# mapleCUL_small-V10_59.net
KiCad netlist of a schematic drawn in EAGLE
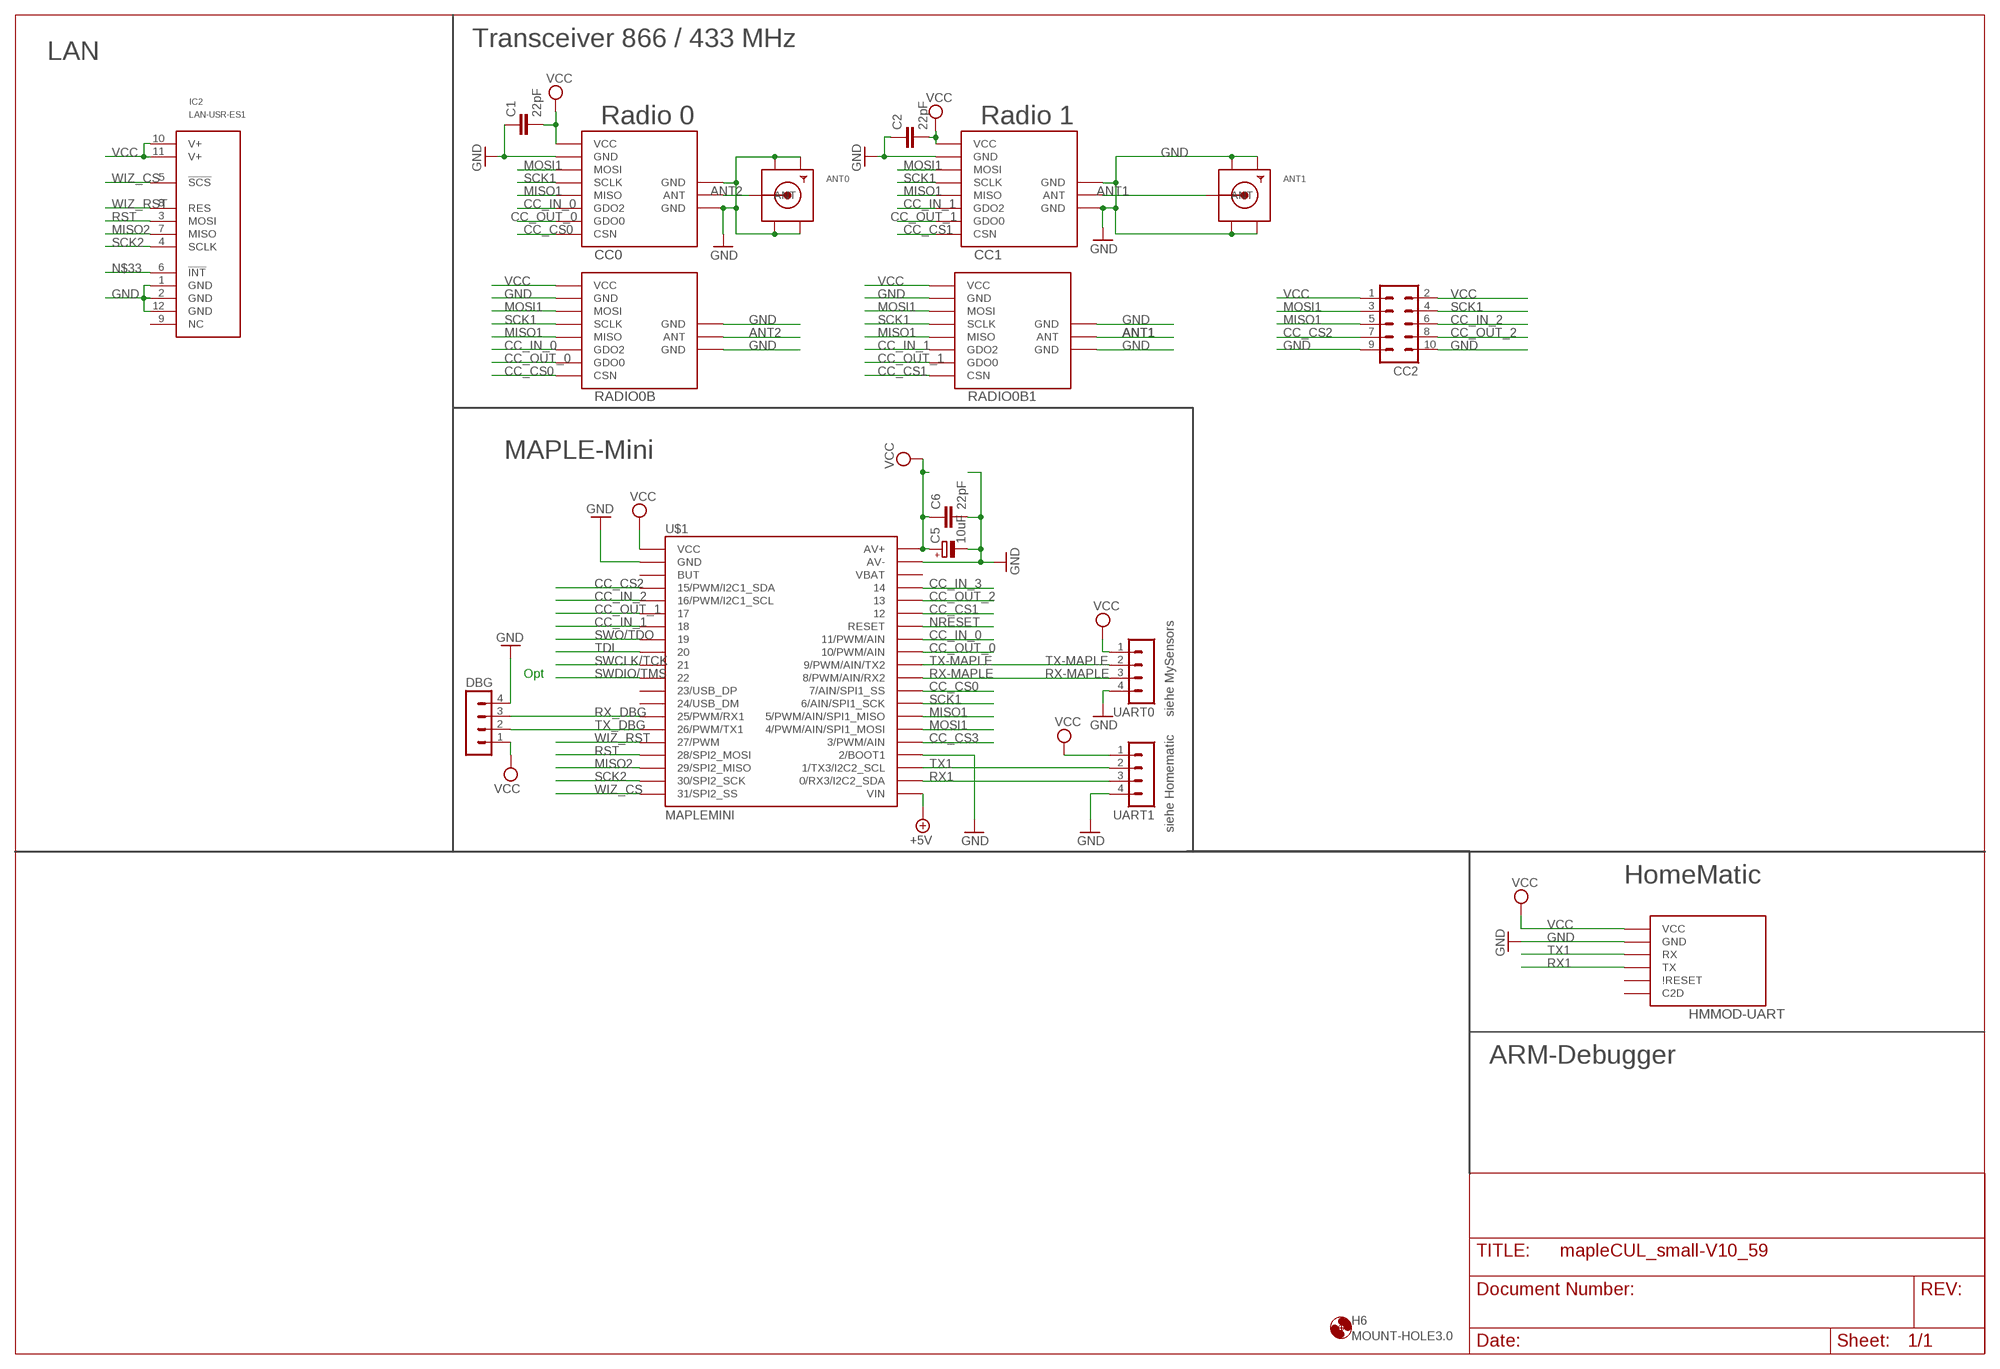
[diagram p0: schematic, sheet 1]

(export (version "E")
  (design (tool "Eeschema 10.0.6"))
  (components
    (comp (ref "ANT0")
      (value "SMACONNECTOR_EDGE_UFL")
      (footprint "eagle-import:SMA_EDGELAUNCH_UFL")
      (libsource (lib "eagle-import") (part "SMACONNECTOR_EDGE_UFL"))
    )
    (comp (ref "ANT1")
      (value "SMACONNECTOR_EDGE_UFL")
      (footprint "eagle-import:SMA_EDGELAUNCH_UFL")
      (libsource (lib "eagle-import") (part "SMACONNECTOR_EDGE_UFL"))
    )
    (comp (ref "C1")
      (value "22pF")
      (footprint "eagle-import:C0805")
      (libsource (lib "eagle-import") (part "C-EUC0805"))
    )
    (comp (ref "C2")
      (value "22pF")
      (footprint "eagle-import:C0805")
      (libsource (lib "eagle-import") (part "C-EUC0805"))
    )
    (comp (ref "C5")
      (value "10uF")
      (footprint "eagle-import:R_2012-12W")
      (libsource (lib "eagle-import") (part "CPOL-EUR/2012-12W"))
    )
    (comp (ref "C6")
      (value "22pF")
      (footprint "eagle-import:C0805")
      (libsource (lib "eagle-import") (part "C-EUC0805"))
    )
    (comp (ref "CC0")
      (value "CC1101")
      (footprint "eagle-import:CC1101_MODULE1_SMD")
      (libsource (lib "eagle-import") (part "wireless_CC1101_MODULE1SMD"))
    )
    (comp (ref "CC1")
      (value "CC1101_MODULE1SMD")
      (footprint "eagle-import:CC1101_MODULE1_SMD")
      (libsource (lib "eagle-import") (part "wireless_CC1101_MODULE1SMD"))
    )
    (comp (ref "CC2")
      (value "MA05-2")
      (footprint "eagle-import:MA05-2")
      (libsource (lib "eagle-import") (part "MA05-2"))
    )
    (comp (ref "DBG")
      (value "MA04-1")
      (footprint "eagle-import:MA04-1")
      (libsource (lib "eagle-import") (part "MA04-1"))
    )
    (comp (ref "H6")
      (value "MOUNT-HOLE3.0")
      (footprint "eagle-import:3,0")
      (libsource (lib "eagle-import") (part "MOUNT-HOLE3.0"))
    )
    (comp (ref "HMMOD-UART")
      (value "HM-MOD-UARTDIL")
      (footprint "eagle-import:HM-MOD-UART-DIL")
      (libsource (lib "eagle-import") (part "HM-MOD-UARTDIL"))
    )
    (comp (ref "IC2")
      (value "LAN-USR-ES1")
      (footprint "eagle-import:USR-ES1")
      (libsource (lib "eagle-import") (part "LAN-USR-ES1"))
    )
    (comp (ref "RADIO0B")
      (value "CC1101_MODULE1SMALL")
      (footprint "eagle-import:CC1101_MODULE1_SMD")
      (libsource (lib "eagle-import") (part "CC1101_MODULE1SMALL"))
    )
    (comp (ref "RADIO0B1")
      (value "CC1101_MODULE1SMD")
      (footprint "eagle-import:CC1101_MODULE1_SMD")
      (libsource (lib "eagle-import") (part "CC1101_MODULE1SMD"))
    )
    (comp (ref "U$1")
      (value "MAPLEMINI")
      (footprint "eagle-import:20-DIP")
      (libsource (lib "eagle-import") (part "MAPLEMINI"))
    )
    (comp (ref "UART0")
      (value "MA04-1")
      (footprint "eagle-import:MA04-1")
      (libsource (lib "eagle-import") (part "MA04-1"))
    )
    (comp (ref "UART1")
      (value "MA04-1")
      (footprint "eagle-import:MA04-1")
      (libsource (lib "eagle-import") (part "MA04-1"))
    )
  )
  (nets
    (net (code "1") (name "+5V") (class "Default")
      (node (ref "U$1") (pin "21") (pinfunction "VIN_21") (pintype "bidirectional"))
    )
    (net (code "2") (name "/ANT1") (class "Default")
      (node (ref "ANT1") (pin "P") (pinfunction "ANT_P") (pintype "bidirectional"))
      (node (ref "CC1") (pin "ANT") (pinfunction "ANT_ANT") (pintype "output"))
      (node (ref "RADIO0B1") (pin "ANT") (pinfunction "ANT_ANT") (pintype "output"))
    )
    (net (code "3") (name "/ANT2") (class "Default")
      (node (ref "ANT0") (pin "P") (pinfunction "ANT_P") (pintype "bidirectional"))
      (node (ref "CC0") (pin "ANT") (pinfunction "ANT_ANT") (pintype "output"))
      (node (ref "RADIO0B") (pin "ANT") (pinfunction "ANT_ANT") (pintype "output"))
    )
    (net (code "4") (name "/CC_CS0") (class "Default")
      (node (ref "CC0") (pin "CSN") (pinfunction "CSN_CSN") (pintype "bidirectional"))
      (node (ref "RADIO0B") (pin "CSN") (pinfunction "CSN_CSN") (pintype "bidirectional"))
      (node (ref "U$1") (pin "29") (pinfunction "7/AIN/SPI1_SS_29") (pintype "bidirectional"))
    )
    (net (code "5") (name "/CC_CS1") (class "Default")
      (node (ref "CC1") (pin "CSN") (pinfunction "CSN_CSN") (pintype "bidirectional"))
      (node (ref "RADIO0B1") (pin "CSN") (pinfunction "CSN_CSN") (pintype "bidirectional"))
      (node (ref "U$1") (pin "35") (pinfunction "12_35") (pintype "bidirectional"))
    )
    (net (code "6") (name "/CC_CS2") (class "Default")
      (node (ref "CC2") (pin "7") (pinfunction "7_7") (pintype "passive"))
      (node (ref "U$1") (pin "4") (pinfunction "15/PWM/I2C1_SDA_4") (pintype "bidirectional"))
    )
    (net (code "7") (name "/CC_CS3") (class "Default")
      (node (ref "U$1") (pin "25") (pinfunction "3/PWM/AIN_25") (pintype "bidirectional"))
    )
    (net (code "8") (name "/CC_IN_0") (class "Default")
      (node (ref "CC0") (pin "GDO2") (pinfunction "GDO2_GDO2") (pintype "bidirectional"))
      (node (ref "RADIO0B") (pin "GDO2") (pinfunction "GDO2_GDO2") (pintype "bidirectional"))
      (node (ref "U$1") (pin "33") (pinfunction "11/PWM/AIN_33") (pintype "bidirectional"))
    )
    (net (code "9") (name "/CC_IN_1") (class "Default")
      (node (ref "CC1") (pin "GDO2") (pinfunction "GDO2_GDO2") (pintype "bidirectional"))
      (node (ref "RADIO0B1") (pin "GDO2") (pinfunction "GDO2_GDO2") (pintype "bidirectional"))
      (node (ref "U$1") (pin "7") (pinfunction "18_7") (pintype "bidirectional"))
    )
    (net (code "10") (name "/CC_IN_2") (class "Default")
      (node (ref "CC2") (pin "6") (pinfunction "6_6") (pintype "passive"))
      (node (ref "U$1") (pin "5") (pinfunction "16/PWM/I2C1_SCL_5") (pintype "bidirectional"))
    )
    (net (code "11") (name "/CC_IN_3") (class "Default")
      (node (ref "U$1") (pin "37") (pinfunction "14_37") (pintype "bidirectional"))
    )
    (net (code "12") (name "/CC_OUT_0") (class "Default")
      (node (ref "CC0") (pin "GDO0") (pinfunction "GDO0_GDO0") (pintype "bidirectional"))
      (node (ref "RADIO0B") (pin "GDO0") (pinfunction "GDO0_GDO0") (pintype "bidirectional"))
      (node (ref "U$1") (pin "32") (pinfunction "10/PWM/AIN_32") (pintype "bidirectional"))
    )
    (net (code "13") (name "/CC_OUT_1") (class "Default")
      (node (ref "CC1") (pin "GDO0") (pinfunction "GDO0_GDO0") (pintype "bidirectional"))
      (node (ref "RADIO0B1") (pin "GDO0") (pinfunction "GDO0_GDO0") (pintype "bidirectional"))
      (node (ref "U$1") (pin "6") (pinfunction "17_6") (pintype "bidirectional"))
    )
    (net (code "14") (name "/CC_OUT_2") (class "Default")
      (node (ref "CC2") (pin "8") (pinfunction "8_8") (pintype "passive"))
      (node (ref "U$1") (pin "36") (pinfunction "13_36") (pintype "bidirectional"))
    )
    (net (code "15") (name "/MISO1") (class "Default")
      (node (ref "CC0") (pin "MISO") (pinfunction "MISO_MISO") (pintype "bidirectional"))
      (node (ref "CC1") (pin "MISO") (pinfunction "MISO_MISO") (pintype "bidirectional"))
      (node (ref "CC2") (pin "5") (pinfunction "5_5") (pintype "passive"))
      (node (ref "RADIO0B") (pin "MISO") (pinfunction "MISO_MISO") (pintype "bidirectional"))
      (node (ref "RADIO0B1") (pin "MISO") (pinfunction "MISO_MISO") (pintype "bidirectional"))
      (node (ref "U$1") (pin "27") (pinfunction "5/PWM/AIN/SPI1_MISO_27") (pintype "bidirectional"))
    )
    (net (code "16") (name "/MISO2") (class "Default")
      (node (ref "IC2") (pin "7") (pinfunction "MISO_7") (pintype "bidirectional"))
      (node (ref "U$1") (pin "18") (pinfunction "29/SPI2_MISO_18") (pintype "bidirectional"))
    )
    (net (code "17") (name "/MOSI1") (class "Default")
      (node (ref "CC0") (pin "MOSI") (pinfunction "MOSI_MOSI") (pintype "bidirectional"))
      (node (ref "CC1") (pin "MOSI") (pinfunction "MOSI_MOSI") (pintype "bidirectional"))
      (node (ref "CC2") (pin "3") (pinfunction "3_3") (pintype "passive"))
      (node (ref "RADIO0B") (pin "MOSI") (pinfunction "MOSI_MOSI") (pintype "bidirectional"))
      (node (ref "RADIO0B1") (pin "MOSI") (pinfunction "MOSI_MOSI") (pintype "bidirectional"))
      (node (ref "U$1") (pin "26") (pinfunction "4/PWM/AIN/SPI1_MOSI_26") (pintype "bidirectional"))
    )
    (net (code "18") (name "/N$33") (class "Default")
      (node (ref "IC2") (pin "6") (pinfunction "~{INT}_6") (pintype "output"))
    )
    (net (code "19") (name "/NRESET") (class "Default")
      (node (ref "U$1") (pin "34") (pinfunction "RESET_34") (pintype "bidirectional"))
    )
    (net (code "20") (name "/RST") (class "Default")
      (node (ref "IC2") (pin "3") (pinfunction "MOSI_3") (pintype "bidirectional"))
      (node (ref "U$1") (pin "17") (pinfunction "28/SPI2_MOSI_17") (pintype "bidirectional"))
    )
    (net (code "21") (name "/RX-MAPLE") (class "Default")
      (node (ref "U$1") (pin "30") (pinfunction "8/PWM/AIN/RX2_30") (pintype "bidirectional"))
      (node (ref "UART0") (pin "3") (pinfunction "3_3") (pintype "passive"))
    )
    (net (code "22") (name "/RX1") (class "Default")
      (node (ref "HMMOD-UART") (pin "5") (pinfunction "TX_5") (pintype "bidirectional"))
      (node (ref "U$1") (pin "22") (pinfunction "0/RX3/I2C2_SDA_22") (pintype "bidirectional"))
      (node (ref "UART1") (pin "3") (pinfunction "3_3") (pintype "passive"))
    )
    (net (code "23") (name "/RX_DBG") (class "Default")
      (node (ref "DBG") (pin "3") (pinfunction "3_3") (pintype "passive"))
      (node (ref "U$1") (pin "14") (pinfunction "25/PWM/RX1_14") (pintype "bidirectional"))
    )
    (net (code "24") (name "/SCK1") (class "Default")
      (node (ref "CC0") (pin "SCLK") (pinfunction "SCLK_SCLK") (pintype "bidirectional"))
      (node (ref "CC1") (pin "SCLK") (pinfunction "SCLK_SCLK") (pintype "bidirectional"))
      (node (ref "CC2") (pin "4") (pinfunction "4_4") (pintype "passive"))
      (node (ref "RADIO0B") (pin "SCLK") (pinfunction "SCLK_SCLK") (pintype "bidirectional"))
      (node (ref "RADIO0B1") (pin "SCLK") (pinfunction "SCLK_SCLK") (pintype "bidirectional"))
      (node (ref "U$1") (pin "28") (pinfunction "6/AIN/SPI1_SCK_28") (pintype "bidirectional"))
    )
    (net (code "25") (name "/SCK2") (class "Default")
      (node (ref "IC2") (pin "4") (pinfunction "SCLK_4") (pintype "input"))
      (node (ref "U$1") (pin "19") (pinfunction "30/SPI2_SCK_19") (pintype "bidirectional"))
    )
    (net (code "26") (name "/SWCLK{slash}TCK") (class "Default")
      (node (ref "U$1") (pin "10") (pinfunction "21_10") (pintype "bidirectional"))
    )
    (net (code "27") (name "/SWDIO{slash}TMS") (class "Default")
      (node (ref "U$1") (pin "11") (pinfunction "22_11") (pintype "bidirectional"))
    )
    (net (code "28") (name "/SWO{slash}TDO") (class "Default")
      (node (ref "U$1") (pin "8") (pinfunction "19_8") (pintype "bidirectional"))
    )
    (net (code "29") (name "/TDI") (class "Default")
      (node (ref "U$1") (pin "9") (pinfunction "20_9") (pintype "bidirectional"))
    )
    (net (code "30") (name "/TX-MAPLE") (class "Default")
      (node (ref "U$1") (pin "31") (pinfunction "9/PWM/AIN/TX2_31") (pintype "bidirectional"))
      (node (ref "UART0") (pin "2") (pinfunction "2_2") (pintype "passive"))
    )
    (net (code "31") (name "/TX1") (class "Default")
      (node (ref "HMMOD-UART") (pin "6") (pinfunction "RX_6") (pintype "bidirectional"))
      (node (ref "U$1") (pin "23") (pinfunction "1/TX3/I2C2_SCL_23") (pintype "bidirectional"))
      (node (ref "UART1") (pin "2") (pinfunction "2_2") (pintype "passive"))
    )
    (net (code "32") (name "/TX_DBG") (class "Default")
      (node (ref "DBG") (pin "2") (pinfunction "2_2") (pintype "passive"))
      (node (ref "U$1") (pin "15") (pinfunction "26/PWM/TX1_15") (pintype "bidirectional"))
    )
    (net (code "33") (name "/WIZ_CS") (class "Default")
      (node (ref "IC2") (pin "5") (pinfunction "~{SCS}_5") (pintype "input"))
      (node (ref "U$1") (pin "20") (pinfunction "31/SPI2_SS_20") (pintype "bidirectional"))
    )
    (net (code "34") (name "/WIZ_RST") (class "Default")
      (node (ref "IC2") (pin "8") (pinfunction "RES_8") (pintype "input"))
      (node (ref "U$1") (pin "16") (pinfunction "27/PWM_16") (pintype "bidirectional"))
    )
    (net (code "35") (name "GND") (class "Default")
      (node (ref "ANT0") (pin "GND@1") (pinfunction "GND1_GND@1") (pintype "power_in"))
      (node (ref "ANT0") (pin "GND@2") (pinfunction "GND2_GND@2") (pintype "power_in"))
      (node (ref "ANT0") (pin "GND@3") (pinfunction "GND3_GND@3") (pintype "power_in"))
      (node (ref "ANT0") (pin "GND@4") (pinfunction "GND4_GND@4") (pintype "power_in"))
      (node (ref "ANT1") (pin "GND@1") (pinfunction "GND1_GND@1") (pintype "power_in"))
      (node (ref "ANT1") (pin "GND@2") (pinfunction "GND2_GND@2") (pintype "power_in"))
      (node (ref "ANT1") (pin "GND@3") (pinfunction "GND3_GND@3") (pintype "power_in"))
      (node (ref "ANT1") (pin "GND@4") (pinfunction "GND4_GND@4") (pintype "power_in"))
      (node (ref "C1") (pin "1") (pinfunction "1_1") (pintype "passive"))
      (node (ref "C2") (pin "1") (pinfunction "1_1") (pintype "passive"))
      (node (ref "C5") (pin "-") (pinfunction "-_-") (pintype "passive"))
      (node (ref "C6") (pin "2") (pinfunction "2_2") (pintype "passive"))
      (node (ref "CC0") (pin "GND@0") (pinfunction "GND_GND@0") (pintype "power_in"))
      (node (ref "CC0") (pin "GND@1") (pinfunction "GND_GND@1") (pintype "power_in"))
      (node (ref "CC0") (pin "GND@2") (pinfunction "GND_GND@2") (pintype "power_in"))
      (node (ref "CC1") (pin "GND@0") (pinfunction "GND_GND@0") (pintype "power_in"))
      (node (ref "CC1") (pin "GND@1") (pinfunction "GND_GND@1") (pintype "power_in"))
      (node (ref "CC1") (pin "GND@2") (pinfunction "GND_GND@2") (pintype "power_in"))
      (node (ref "CC2") (pin "10") (pinfunction "10_10") (pintype "passive"))
      (node (ref "CC2") (pin "9") (pinfunction "9_9") (pintype "passive"))
      (node (ref "DBG") (pin "4") (pinfunction "4_4") (pintype "passive"))
      (node (ref "HMMOD-UART") (pin "2") (pinfunction "GND_2") (pintype "power_in"))
      (node (ref "IC2") (pin "1") (pinfunction "GND_1") (pintype "power_in"))
      (node (ref "IC2") (pin "12") (pinfunction "GND_12") (pintype "power_in"))
      (node (ref "IC2") (pin "2") (pinfunction "GND_2") (pintype "power_in"))
      (node (ref "RADIO0B") (pin "GND@0") (pinfunction "GND_GND@0") (pintype "power_in"))
      (node (ref "RADIO0B") (pin "GND@1") (pinfunction "GND_GND@1") (pintype "power_in"))
      (node (ref "RADIO0B") (pin "GND@2") (pinfunction "GND_GND@2") (pintype "power_in"))
      (node (ref "RADIO0B1") (pin "GND@0") (pinfunction "GND_GND@0") (pintype "power_in"))
      (node (ref "RADIO0B1") (pin "GND@1") (pinfunction "GND_GND@1") (pintype "power_in"))
      (node (ref "RADIO0B1") (pin "GND@2") (pinfunction "GND_GND@2") (pintype "power_in"))
      (node (ref "U$1") (pin "2") (pinfunction "GND_2") (pintype "bidirectional"))
      (node (ref "U$1") (pin "24") (pinfunction "2/BOOT1_24") (pintype "bidirectional"))
      (node (ref "U$1") (pin "39") (pinfunction "AV-_39") (pintype "bidirectional"))
      (node (ref "UART0") (pin "4") (pinfunction "4_4") (pintype "passive"))
      (node (ref "UART1") (pin "4") (pinfunction "4_4") (pintype "passive"))
    )
    (net (code "36") (name "VCC") (class "Default")
      (node (ref "C1") (pin "2") (pinfunction "2_2") (pintype "passive"))
      (node (ref "C2") (pin "2") (pinfunction "2_2") (pintype "passive"))
      (node (ref "C5") (pin "+") (pinfunction "+_+") (pintype "passive"))
      (node (ref "C6") (pin "1") (pinfunction "1_1") (pintype "passive"))
      (node (ref "CC0") (pin "VCC") (pinfunction "VCC_VCC") (pintype "power_in"))
      (node (ref "CC1") (pin "VCC") (pinfunction "VCC_VCC") (pintype "power_in"))
      (node (ref "CC2") (pin "1") (pinfunction "1_1") (pintype "passive"))
      (node (ref "CC2") (pin "2") (pinfunction "2_2") (pintype "passive"))
      (node (ref "DBG") (pin "1") (pinfunction "1_1") (pintype "passive"))
      (node (ref "HMMOD-UART") (pin "1") (pinfunction "VCC_1") (pintype "power_in"))
      (node (ref "IC2") (pin "10") (pinfunction "V+_10") (pintype "power_in"))
      (node (ref "IC2") (pin "11") (pinfunction "V+_11") (pintype "power_in"))
      (node (ref "RADIO0B") (pin "VCC") (pinfunction "VCC_VCC") (pintype "power_in"))
      (node (ref "RADIO0B1") (pin "VCC") (pinfunction "VCC_VCC") (pintype "power_in"))
      (node (ref "U$1") (pin "1") (pinfunction "VCC_1") (pintype "bidirectional"))
      (node (ref "U$1") (pin "40") (pinfunction "AV+_40") (pintype "bidirectional"))
      (node (ref "UART0") (pin "1") (pinfunction "1_1") (pintype "passive"))
      (node (ref "UART1") (pin "1") (pinfunction "1_1") (pintype "passive"))
    )
    (net (code "37") (name "unconnected-(HMMOD-UART-C2D-Pad3)") (class "Default")
      (node (ref "HMMOD-UART") (pin "3") (pinfunction "C2D_3") (pintype "bidirectional"))
    )
    (net (code "38") (name "unconnected-(HMMOD-UART-\\~{RESET}-Pad4)") (class "Default")
      (node (ref "HMMOD-UART") (pin "4") (pinfunction "\\~{RESET}_4") (pintype "bidirectional"))
    )
    (net (code "39") (name "unconnected-(IC2-NC-Pad9)") (class "Default")
      (node (ref "IC2") (pin "9") (pinfunction "NC_9") (pintype "no_connect"))
    )
    (net (code "40") (name "unconnected-(U$1-23{slash}USB_DP-Pad12)") (class "Default")
      (node (ref "U$1") (pin "12") (pinfunction "23/USB_DP_12") (pintype "bidirectional"))
    )
    (net (code "41") (name "unconnected-(U$1-24{slash}USB_DM-Pad13)") (class "Default")
      (node (ref "U$1") (pin "13") (pinfunction "24/USB_DM_13") (pintype "bidirectional"))
    )
    (net (code "42") (name "unconnected-(U$1-BUT-Pad3)") (class "Default")
      (node (ref "U$1") (pin "3") (pinfunction "BUT_3") (pintype "bidirectional"))
    )
    (net (code "43") (name "unconnected-(U$1-VBAT-Pad38)") (class "Default")
      (node (ref "U$1") (pin "38") (pinfunction "VBAT_38") (pintype "bidirectional"))
    )
  )
)
